# GPIO_Expander.net
KiCad netlist of a schematic drawn in Altium Designer
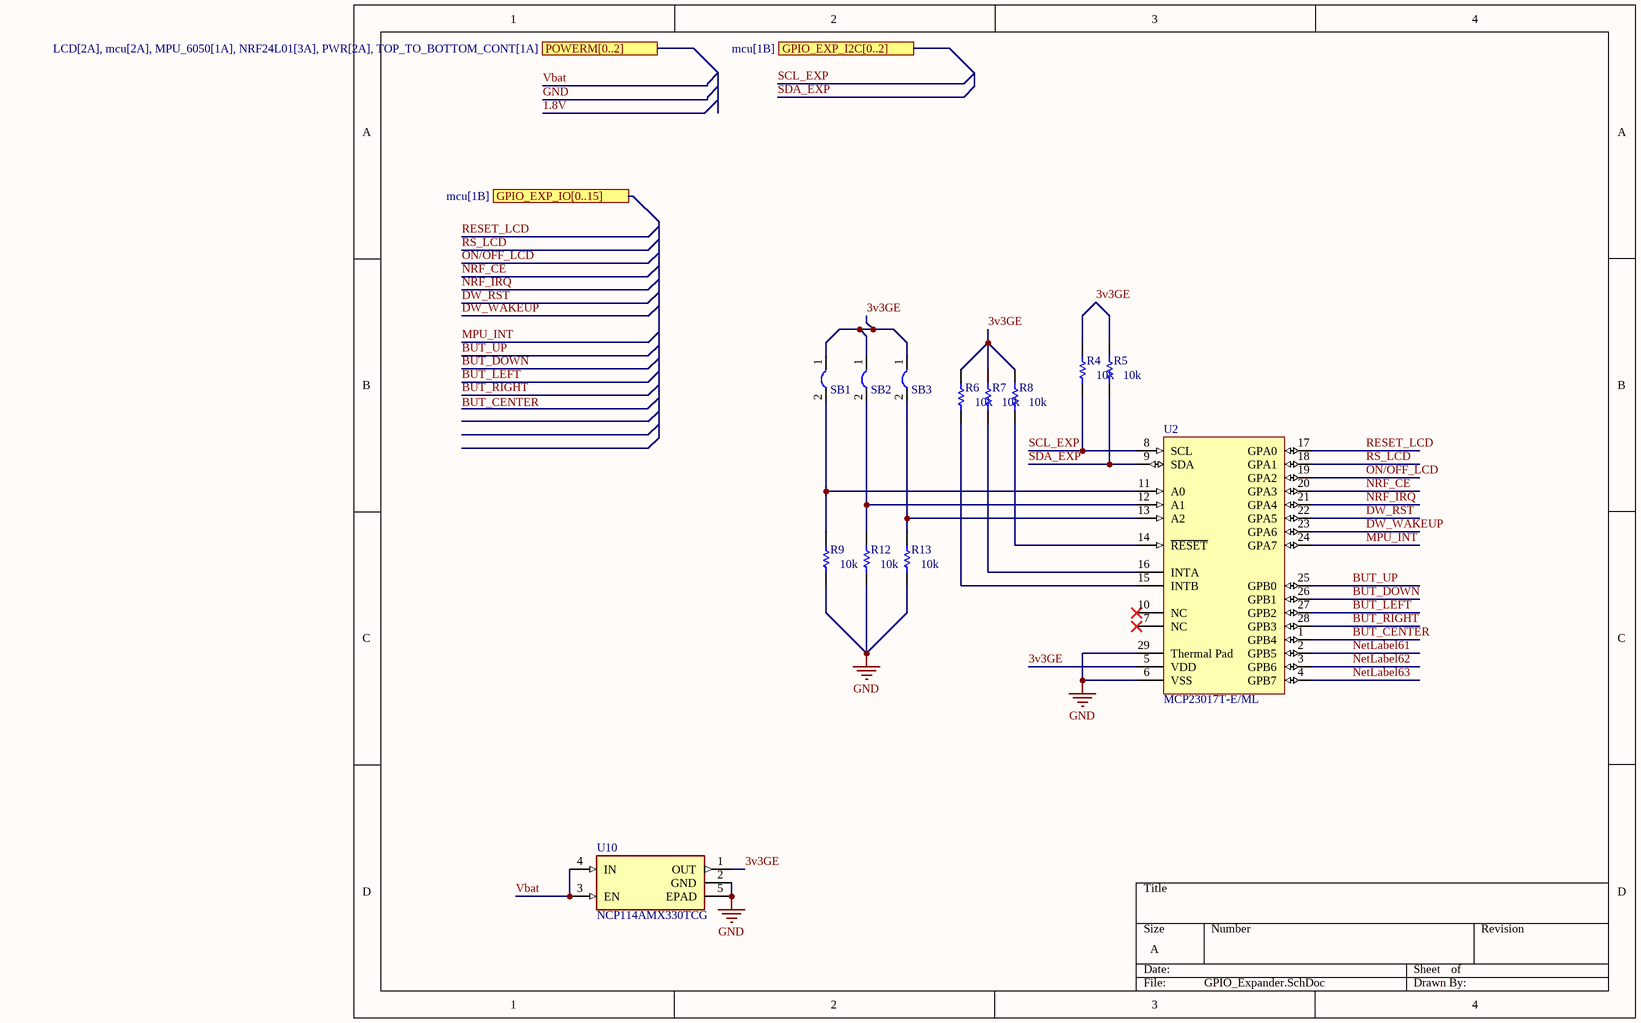
[diagram p0: GPIO_Expander.SchDoc]

(export (version "E")
  (design (tool "Eeschema 10.0.6"))
  (components
    (comp (ref "R4")
      (value "0402WGF1002TCE")
      (footprint "RESC1005X40X25LL05T10")
      (fields
        (field (name "MANUFACTURER") "UNI-ROYAL(Uniroyal Elec)")
        (field (name "JLCPCB PART #") "C25744")
        (field (name "RESISTANCE") "10k")
      )
      (libsource (lib "Altium Content Vault") (part "RES"))
    )
    (comp (ref "R5")
      (value "0402WGF1002TCE")
      (footprint "RESC1005X40X25LL05T10")
      (fields
        (field (name "MANUFACTURER") "UNI-ROYAL(Uniroyal Elec)")
        (field (name "JLCPCB PART #") "C25744")
        (field (name "RESISTANCE") "10k")
      )
      (libsource (lib "Altium Content Vault") (part "RES"))
    )
    (comp (ref "R6")
      (value "0402WGF1002TCE")
      (footprint "RESC1005X40X25LL05T10")
      (fields
        (field (name "MANUFACTURER") "UNI-ROYAL(Uniroyal Elec)")
        (field (name "JLCPCB PART #") "C25744")
        (field (name "RESISTANCE") "10k")
      )
      (libsource (lib "Altium Content Vault") (part "RES"))
    )
    (comp (ref "R7")
      (value "0402WGF1002TCE")
      (footprint "RESC1005X40X25LL05T10")
      (fields
        (field (name "MANUFACTURER") "UNI-ROYAL(Uniroyal Elec)")
        (field (name "JLCPCB PART #") "C25744")
        (field (name "RESISTANCE") "10k")
      )
      (libsource (lib "Altium Content Vault") (part "RES"))
    )
    (comp (ref "R8")
      (value "0402WGF1002TCE")
      (footprint "RESC1005X40X25LL05T10")
      (fields
        (field (name "MANUFACTURER") "UNI-ROYAL(Uniroyal Elec)")
        (field (name "JLCPCB PART #") "C25744")
        (field (name "RESISTANCE") "10k")
      )
      (libsource (lib "Altium Content Vault") (part "RES"))
    )
    (comp (ref "R9")
      (value "0402WGF1002TCE")
      (footprint "RESC1005X40X25LL05T10")
      (fields
        (field (name "MANUFACTURER") "UNI-ROYAL(Uniroyal Elec)")
        (field (name "JLCPCB PART #") "C25744")
        (field (name "RESISTANCE") "10k")
      )
      (libsource (lib "Altium Content Vault") (part "RES"))
    )
    (comp (ref "R12")
      (value "0402WGF1002TCE")
      (footprint "RESC1005X40X25LL05T10")
      (fields
        (field (name "MANUFACTURER") "UNI-ROYAL(Uniroyal Elec)")
        (field (name "JLCPCB PART #") "C25744")
        (field (name "RESISTANCE") "10k")
      )
      (libsource (lib "Altium Content Vault") (part "RES"))
    )
    (comp (ref "R13")
      (value "0402WGF1002TCE")
      (footprint "RESC1005X40X25LL05T10")
      (fields
        (field (name "MANUFACTURER") "UNI-ROYAL(Uniroyal Elec)")
        (field (name "JLCPCB PART #") "C25744")
        (field (name "RESISTANCE") "10k")
      )
      (libsource (lib "Altium Content Vault") (part "RES"))
    )
    (comp (ref "SB1")
      (value "Jumper")
      (footprint "Jumper")
      (libsource (lib "Integrated_Library2") (part "Jumper"))
    )
    (comp (ref "SB2")
      (value "Jumper")
      (footprint "Jumper")
      (libsource (lib "Integrated_Library2") (part "Jumper"))
    )
    (comp (ref "SB3")
      (value "Jumper")
      (footprint "Jumper")
      (libsource (lib "Integrated_Library2") (part "Jumper"))
    )
    (comp (ref "U2")
      (value "MCP23017T-E/ML")
      (footprint "QFN-ML28_M")
      (description "16-Bit I/O Expander with Serial Interface, 28-Pin QFN, Extended Temperature, Tape and Reel")
      (fields (field (name "MANUFACTURER") "Microchip Tech") (field (name "JLCPCB PART #") "C629439"))
      (libsource (lib "Altium Content Vault") (part "PR-BUSIC-MCP23017-29"))
    )
    (comp (ref "U10")
      (value "NCP114AMX330TCG")
      (footprint "REG_NCP114AMX330TCG")
      (description "Linear Voltage Regulator IC Positive Fixed 1 Output 300mA 4-UDFN (1.0x1.0)")
      (fields (field (name "MANUFACTURER") "onsemi") (field (name "JLCPCB PART #") "C133056"))
      (libsource (lib "NCP114AMX330TCG") (part "NCP114AMX330TCG"))
    )
  )
  (nets
    (net (code "24") (name "/3v3GE") (class "Default")
      (node (ref "R4") (pin "2") (pinfunction "2_2") (pintype "passive"))
      (node (ref "R5") (pin "2") (pinfunction "2_2") (pintype "passive"))
      (node (ref "R6") (pin "2") (pinfunction "2_2") (pintype "passive"))
      (node (ref "R7") (pin "2") (pinfunction "2_2") (pintype "passive"))
      (node (ref "R8") (pin "2") (pinfunction "2_2") (pintype "passive"))
      (node (ref "SB1") (pin "1") (pinfunction "1_1") (pintype "passive"))
      (node (ref "SB2") (pin "1") (pinfunction "1_1") (pintype "passive"))
      (node (ref "SB3") (pin "1") (pinfunction "1_1") (pintype "passive"))
      (node (ref "U10") (pin "1") (pinfunction "OUT_1") (pintype "output"))
      (node (ref "U2") (pin "5") (pinfunction "VDD_5") (pintype "power_in"))
    )
    (net (code "25") (name "/BUT_CENTER") (class "Default")
      (node (ref "U2") (pin "1") (pinfunction "GPB4_1") (pintype "bidirectional"))
    )
    (net (code "26") (name "/BUT_DOWN") (class "Default")
      (node (ref "U2") (pin "26") (pinfunction "GPB1_26") (pintype "bidirectional"))
    )
    (net (code "27") (name "/BUT_LEFT") (class "Default")
      (node (ref "U2") (pin "27") (pinfunction "GPB2_27") (pintype "bidirectional"))
    )
    (net (code "28") (name "/BUT_RIGHT") (class "Default")
      (node (ref "U2") (pin "28") (pinfunction "GPB3_28") (pintype "bidirectional"))
    )
    (net (code "29") (name "/BUT_UP") (class "Default")
      (node (ref "U2") (pin "25") (pinfunction "GPB0_25") (pintype "bidirectional"))
    )
    (net (code "30") (name "/DW_RST") (class "Default")
      (node (ref "U2") (pin "22") (pinfunction "GPA5_22") (pintype "bidirectional"))
    )
    (net (code "31") (name "/DW_WAKEUP") (class "Default")
      (node (ref "U2") (pin "23") (pinfunction "GPA6_23") (pintype "bidirectional"))
    )
    (net (code "34") (name "/MPU_INT") (class "Default")
      (node (ref "U2") (pin "24") (pinfunction "GPA7_24") (pintype "bidirectional"))
    )
    (net (code "35") (name "/NRF_CE") (class "Default")
      (node (ref "U2") (pin "20") (pinfunction "GPA3_20") (pintype "bidirectional"))
    )
    (net (code "36") (name "/NRF_IRQ") (class "Default")
      (node (ref "U2") (pin "21") (pinfunction "GPA4_21") (pintype "bidirectional"))
    )
    (net (code "37") (name "/NetLabel61") (class "Default")
      (node (ref "U2") (pin "2") (pinfunction "GPB5_2") (pintype "bidirectional"))
    )
    (net (code "38") (name "/NetLabel62") (class "Default")
      (node (ref "U2") (pin "3") (pinfunction "GPB6_3") (pintype "bidirectional"))
    )
    (net (code "39") (name "/NetLabel63") (class "Default")
      (node (ref "U2") (pin "4") (pinfunction "GPB7_4") (pintype "bidirectional"))
    )
    (net (code "40") (name "/ON{slash}OFF_LCD") (class "Default")
      (node (ref "U2") (pin "19") (pinfunction "GPA2_19") (pintype "bidirectional"))
    )
    (net (code "42") (name "/RESET_LCD") (class "Default")
      (node (ref "U2") (pin "17") (pinfunction "GPA0_17") (pintype "bidirectional"))
    )
    (net (code "43") (name "/RS_LCD") (class "Default")
      (node (ref "U2") (pin "18") (pinfunction "GPA1_18") (pintype "bidirectional"))
    )
    (net (code "44") (name "/SCL_EXP") (class "Default")
      (node (ref "R4") (pin "1") (pinfunction "1_1") (pintype "passive"))
      (node (ref "U2") (pin "8") (pinfunction "SCL_8") (pintype "input"))
    )
    (net (code "45") (name "/SDA_EXP") (class "Default")
      (node (ref "R5") (pin "1") (pinfunction "1_1") (pintype "passive"))
      (node (ref "U2") (pin "9") (pinfunction "SDA_9") (pintype "bidirectional"))
    )
    (net (code "46") (name "/Vbat") (class "Default")
      (node (ref "U10") (pin "3") (pinfunction "EN_3") (pintype "input"))
      (node (ref "U10") (pin "4") (pinfunction "IN_4") (pintype "input"))
    )
    (net (code "47") (name "GND") (class "Default")
      (node (ref "R12") (pin "1") (pinfunction "1_1") (pintype "passive"))
      (node (ref "R13") (pin "1") (pinfunction "1_1") (pintype "passive"))
      (node (ref "R9") (pin "1") (pinfunction "1_1") (pintype "passive"))
      (node (ref "U10") (pin "2") (pinfunction "GND_2") (pintype "power_in"))
      (node (ref "U10") (pin "5") (pinfunction "EPAD_5") (pintype "passive"))
      (node (ref "U2") (pin "29") (pinfunction "Thermal_Pad_29") (pintype "passive"))
      (node (ref "U2") (pin "6") (pinfunction "VSS_6") (pintype "power_in"))
    )
    (net (code "48") (name "Net-(U2-A0)") (class "Default")
      (node (ref "R9") (pin "2") (pinfunction "2_2") (pintype "passive"))
      (node (ref "SB1") (pin "2") (pinfunction "2_2") (pintype "passive"))
      (node (ref "U2") (pin "11") (pinfunction "A0_11") (pintype "input"))
    )
    (net (code "49") (name "Net-(U2-A1)") (class "Default")
      (node (ref "R12") (pin "2") (pinfunction "2_2") (pintype "passive"))
      (node (ref "SB2") (pin "2") (pinfunction "2_2") (pintype "passive"))
      (node (ref "U2") (pin "12") (pinfunction "A1_12") (pintype "input"))
    )
    (net (code "50") (name "Net-(U2-A2)") (class "Default")
      (node (ref "R13") (pin "2") (pinfunction "2_2") (pintype "passive"))
      (node (ref "SB3") (pin "2") (pinfunction "2_2") (pintype "passive"))
      (node (ref "U2") (pin "13") (pinfunction "A2_13") (pintype "input"))
    )
    (net (code "51") (name "Net-(U2-INTA)") (class "Default")
      (node (ref "R7") (pin "1") (pinfunction "1_1") (pintype "passive"))
      (node (ref "U2") (pin "16") (pinfunction "INTA_16") (pintype "open_collector"))
    )
    (net (code "52") (name "Net-(U2-INTB)") (class "Default")
      (node (ref "R6") (pin "1") (pinfunction "1_1") (pintype "passive"))
      (node (ref "U2") (pin "15") (pinfunction "INTB_15") (pintype "open_collector"))
    )
    (net (code "53") (name "Net-(U2-~{RESET})") (class "Default")
      (node (ref "R8") (pin "1") (pinfunction "1_1") (pintype "passive"))
      (node (ref "U2") (pin "14") (pinfunction "~{RESET}_14") (pintype "input"))
    )
    (net (code "54") (name "unconnected-(U2-NC-Pad7)") (class "Default")
      (node (ref "U2") (pin "7") (pinfunction "NC_7") (pintype "passive+no_connect"))
    )
    (net (code "55") (name "unconnected-(U2-NC-Pad10)") (class "Default")
      (node (ref "U2") (pin "10") (pinfunction "NC_10") (pintype "passive+no_connect"))
    )
  )
)
